# RoboFut.net
KiCad netlist of a schematic drawn in Altium Designer
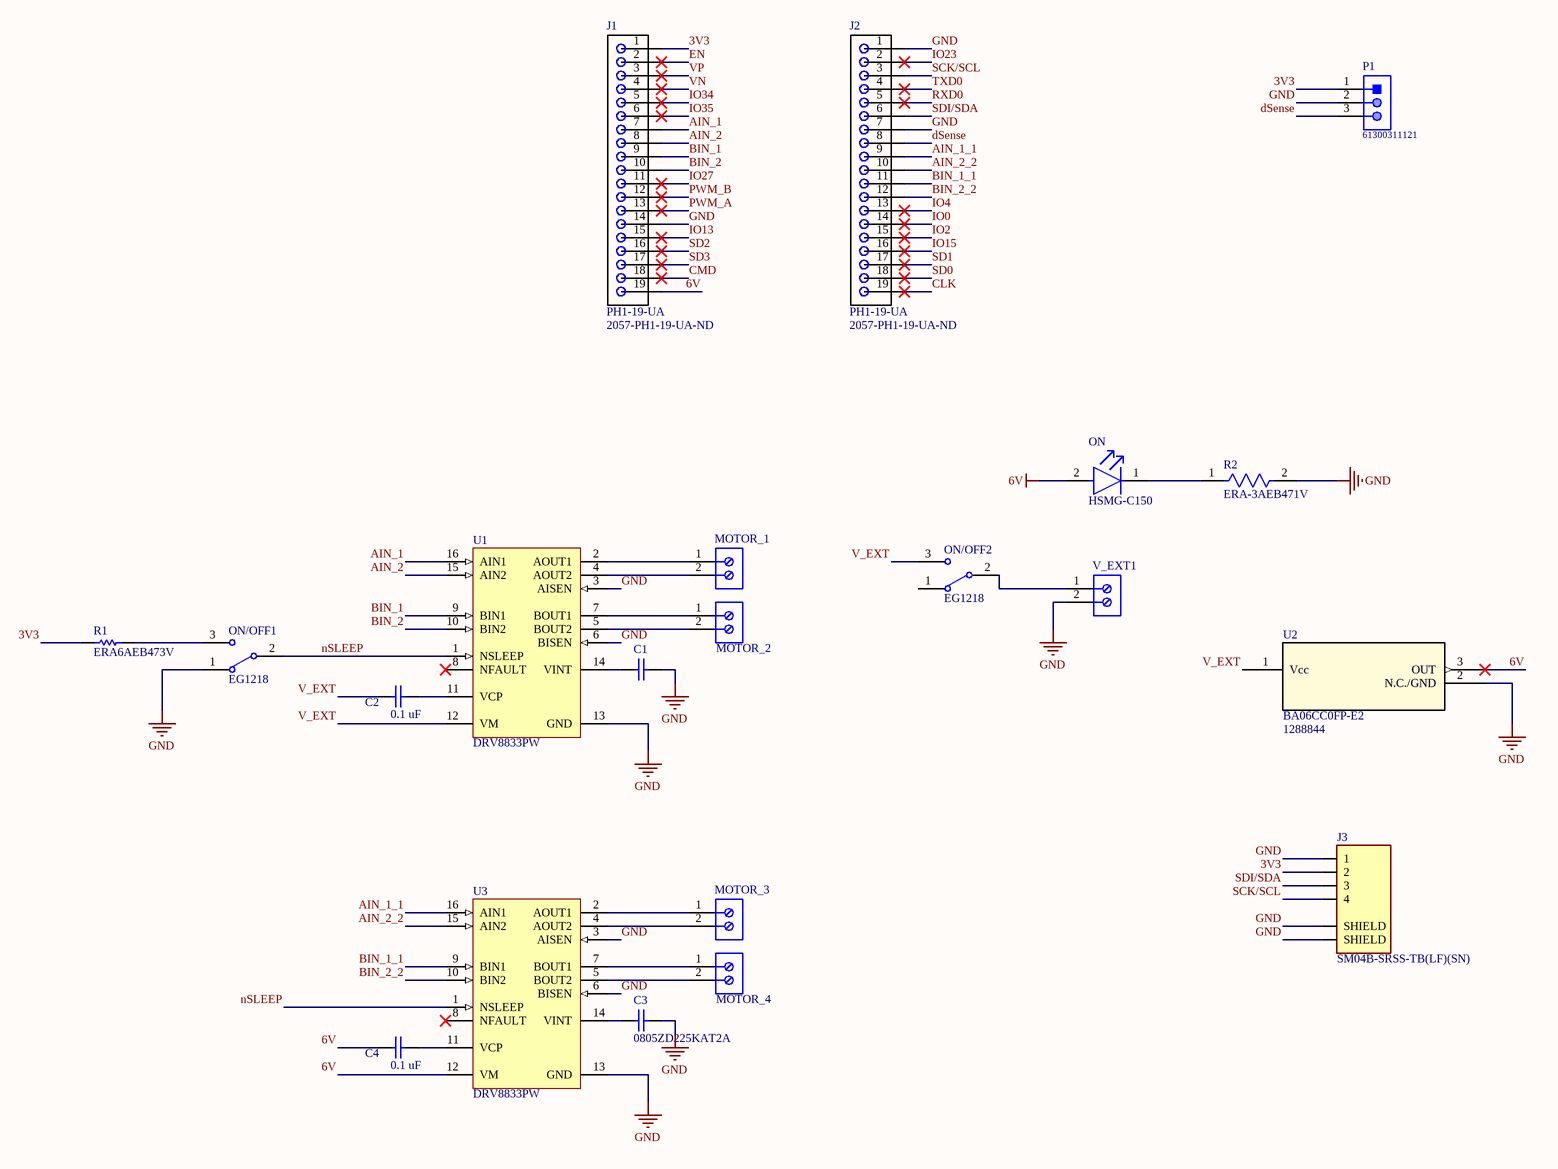
[diagram p0: RoboFut.SchDoc]

(export (version "E")
  (design (tool "Eeschema 10.0.6"))
  (components
    (comp (ref "C1")
      (value "0805ZD225KAT2A")
      (footprint "CAPC2013X140X50ML20T25")
      (description "Chip Capacitor, 2.2 uF, +/- 10%, 10 V, -55 to 85 degC, 0805 (2012 Metric), RoHS, Tape and Reel")
      (fields (field (name "MANUFACTURER") "AVX"))
      (libsource (lib "Altium Content Vault") (part "CAP-NP-2"))
    )
    (comp (ref "C2")
      (value "0.1 uF")
      (footprint "CAPC2013X94X50ML20T25")
      (description "Chip Capacitor, Ceramic, 0.1 uF, 10%, 50 V, 0805, RoHS, Tape and Reel")
      (fields (field (name "MANUFACTURER") "AVX"))
      (libsource (lib "Altium Content Vault") (part "CAP-NP-2"))
    )
    (comp (ref "C3")
      (value "0805ZD225KAT2A")
      (footprint "CAPC2013X140X50ML20T25")
      (description "Chip Capacitor, 2.2 uF, +/- 10%, 10 V, -55 to 85 degC, 0805 (2012 Metric), RoHS, Tape and Reel")
      (fields (field (name "MANUFACTURER") "AVX"))
      (libsource (lib "Altium Content Vault") (part "CAP-NP-2"))
    )
    (comp (ref "C4")
      (value "0.1 uF")
      (footprint "CAPC2013X94X50ML20T25")
      (description "Chip Capacitor, Ceramic, 0.1 uF, 10%, 50 V, 0805, RoHS, Tape and Reel")
      (fields (field (name "MANUFACTURER") "AVX"))
      (libsource (lib "Altium Content Vault") (part "CAP-NP-2"))
    )
    (comp (ref "J1")
      (value "PH1-19-UA")
      (footprint "PH1-19-UA - Socket")
      (description "Connector Header Through Hole 19 position 0.100\" (2.54mm)")
      (fields (field (name "SUPPLIER PART NUMBER 1") "2057-PH1-19-UA-ND"))
      (libsource (lib "Isidro_Library") (part "PH1-19-UA"))
    )
    (comp (ref "J2")
      (value "PH1-19-UA")
      (footprint "PH1-19-UA - Socket")
      (description "Connector Header Through Hole 19 position 0.100\" (2.54mm)")
      (fields (field (name "SUPPLIER PART NUMBER 1") "2057-PH1-19-UA-ND"))
      (libsource (lib "Isidro_Library") (part "PH1-19-UA"))
    )
    (comp (ref "J3")
      (value "SM04B-SRSS-TB(LF)(SN)")
      (footprint "JST_SM04B-SRSS-TB(LF)(SN)")
      (description "Connector Header Surface Mount, Right Angle 4 position 0.039 _1.00mm_")
      (fields (field (name "MF") "JST Sales") (field (name "MP") "SM04B-SRSS-TB_LF__SN_"))
      (libsource (lib "AQIMon") (part "SM04B-SRSS-TB(LF)(SN)"))
    )
    (comp (ref "MOTOR_1")
      (value "691214110002")
      (footprint "691214110002")
      (description "Serie 2141 - 3.50 mm Horizontal Entry Modular with Rising Cage Clamp WR-TBL, 2 pin")
      (fields (field (name "MANUFACTURER") "Wurth Elektronik") (field (name "PUBLISHER") "WurthElektronik"))
      (libsource (lib "Altium Content Vault") (part "WE-CN-1P-F-TB2"))
    )
    (comp (ref "MOTOR_2")
      (value "691214110002")
      (footprint "691214110002")
      (description "Serie 2141 - 3.50 mm Horizontal Entry Modular with Rising Cage Clamp WR-TBL, 2 pin")
      (fields (field (name "MANUFACTURER") "Wurth Elektronik") (field (name "PUBLISHER") "WurthElektronik"))
      (libsource (lib "Altium Content Vault") (part "WE-CN-1P-F-TB2"))
    )
    (comp (ref "MOTOR_3")
      (value "691214110002")
      (footprint "691214110002")
      (description "Serie 2141 - 3.50 mm Horizontal Entry Modular with Rising Cage Clamp WR-TBL, 2 pin")
      (fields (field (name "MANUFACTURER") "Wurth Elektronik") (field (name "PUBLISHER") "WurthElektronik"))
      (libsource (lib "Altium Content Vault") (part "WE-CN-1P-F-TB2"))
    )
    (comp (ref "MOTOR_4")
      (value "691214110002")
      (footprint "691214110002")
      (description "Serie 2141 - 3.50 mm Horizontal Entry Modular with Rising Cage Clamp WR-TBL, 2 pin")
      (fields (field (name "MANUFACTURER") "Wurth Elektronik") (field (name "PUBLISHER") "WurthElektronik"))
      (libsource (lib "Altium Content Vault") (part "WE-CN-1P-F-TB2"))
    )
    (comp (ref "ON")
      (value "HSMG-C150")
      (footprint "FP-HSMG-C150-MFG")
      (description "LED GREEN DIFFUSED 1206 SMD")
      (fields
        (field (name "MANUFACTURER") "Broadcom")
        (field (name "OCTOPART") "https://octopart.com/hsmg-c150-broadcom-71131304")
      )
      (libsource (lib "Altium Content Vault") (part "8706943c75ba83719d021d2fdc84c58"))
    )
    (comp (ref "ON/OFF1")
      (value "EG1218")
      (footprint "ESWI-EG1218_V")
      (description "Slide Switch, 500 V, -20 to 70 degC, 3-Pin THD, RoHS")
      (libsource (lib "Altium Content Vault") (part "SW-SPDT-3_B"))
    )
    (comp (ref "ON/OFF2")
      (value "EG1218")
      (footprint "ESWI-EG1218_V")
      (description "Slide Switch, 500 V, -20 to 70 degC, 3-Pin THD, RoHS")
      (libsource (lib "Altium Content Vault") (part "SW-SPDT-3_B"))
    )
    (comp (ref "P1")
      (value "61300311121")
      (footprint "61300311121")
      (description "THT Vertical Pin Header WR-PHD, Pitch 2.54 mm, Single Row, 3 pins")
      (fields (field (name "MANUFACTURER") "Wurth Elektronik") (field (name "PUBLISHER") "WurthElektronik"))
      (libsource (lib "Altium Content Vault") (part "WE-CN-1P-M-R3"))
    )
    (comp (ref "R1")
      (value "ERA6AEB473V")
      (footprint "RESC2013X60X40ML20T25")
      (fields (field (name "MANUFACTURER") "Panasonic"))
      (libsource (lib "Altium Content Vault") (part "RES"))
    )
    (comp (ref "R2")
      (value "ERA-3AEB471V")
      (footprint "FP-ERA3A-IPC_A")
      (description "RES SMD 470 OHM 0.1% 1/10W 0603")
      (fields (field (name "TOLERANCE") "0.1%"))
      (libsource (lib "Altium Content Vault") (part "8db39607336c341a927600551d01821"))
    )
    (comp (ref "U1")
      (value "DRV8833PW")
      (footprint "PW0016A_M")
      (fields (field (name "MANUFACTURER") "Texas Instruments"))
      (libsource (lib "Altium Content Vault") (part "TI-DRV8833PW-16"))
    )
    (comp (ref "U2")
      (value "BA06CC0FP-E2")
      (footprint "TO252-3_ROM-M")
      (description "Linear Voltage Regulator IC Positive Fixed 1 Output 1A TO-252")
      (fields
        (field (name "SUPPLIER PART NUMBER 1") "1288844")
        (field (name "COPYRIGHT") "Copyright (C) 2022 Ultra Librarian. All rights reserved.")
      )
      (libsource (lib "Isidro_Library") (part "BA06CC0FP-E2"))
    )
    (comp (ref "U3")
      (value "DRV8833PW")
      (footprint "PW0016A_M")
      (fields (field (name "MANUFACTURER") "Texas Instruments"))
      (libsource (lib "Altium Content Vault") (part "TI-DRV8833PW-16"))
    )
    (comp (ref "V_EXT1")
      (value "691214110002")
      (footprint "691214110002")
      (description "Serie 2141 - 3.50 mm Horizontal Entry Modular with Rising Cage Clamp WR-TBL, 2 pin")
      (fields (field (name "MANUFACTURER") "Wurth Elektronik") (field (name "PUBLISHER") "WurthElektronik"))
      (libsource (lib "Altium Content Vault") (part "WE-CN-1P-F-TB2"))
    )
  )
  (nets
    (net (code "1") (name "/3V3") (class "Default")
      (node (ref "J1") (pin "1") (pinfunction "1_1") (pintype "passive"))
      (node (ref "J3") (pin "2") (pinfunction "2_2") (pintype "passive"))
      (node (ref "P1") (pin "1") (pinfunction "1_1") (pintype "passive"))
      (node (ref "R1") (pin "2") (pinfunction "2_2") (pintype "passive"))
    )
    (net (code "2") (name "/AIN_1") (class "Default")
      (node (ref "J1") (pin "7") (pinfunction "7_7") (pintype "passive"))
      (node (ref "U1") (pin "16") (pinfunction "AIN1_16") (pintype "input"))
    )
    (net (code "3") (name "/AIN_1_1") (class "Default")
      (node (ref "J2") (pin "9") (pinfunction "9_9") (pintype "passive"))
      (node (ref "U3") (pin "16") (pinfunction "AIN1_16") (pintype "input"))
    )
    (net (code "4") (name "/AIN_2") (class "Default")
      (node (ref "J1") (pin "8") (pinfunction "8_8") (pintype "passive"))
      (node (ref "U1") (pin "15") (pinfunction "AIN2_15") (pintype "input"))
    )
    (net (code "5") (name "/AIN_2_2") (class "Default")
      (node (ref "J2") (pin "10") (pinfunction "10_10") (pintype "passive"))
      (node (ref "U3") (pin "15") (pinfunction "AIN2_15") (pintype "input"))
    )
    (net (code "6") (name "/BIN_1") (class "Default")
      (node (ref "J1") (pin "9") (pinfunction "9_9") (pintype "passive"))
      (node (ref "U1") (pin "9") (pinfunction "BIN1_9") (pintype "input"))
    )
    (net (code "7") (name "/BIN_1_1") (class "Default")
      (node (ref "J2") (pin "11") (pinfunction "11_11") (pintype "passive"))
      (node (ref "U3") (pin "9") (pinfunction "BIN1_9") (pintype "input"))
    )
    (net (code "8") (name "/BIN_2") (class "Default")
      (node (ref "J1") (pin "10") (pinfunction "10_10") (pintype "passive"))
      (node (ref "U1") (pin "10") (pinfunction "BIN2_10") (pintype "input"))
    )
    (net (code "9") (name "/BIN_2_2") (class "Default")
      (node (ref "J2") (pin "12") (pinfunction "12_12") (pintype "passive"))
      (node (ref "U3") (pin "10") (pinfunction "BIN2_10") (pintype "input"))
    )
    (net (code "10") (name "/CLK") (class "Default")
      (node (ref "J2") (pin "19") (pinfunction "19_19") (pintype "passive+no_connect"))
    )
    (net (code "11") (name "/CMD") (class "Default")
      (node (ref "J1") (pin "18") (pinfunction "18_18") (pintype "passive+no_connect"))
    )
    (net (code "12") (name "/EN") (class "Default")
      (node (ref "J1") (pin "2") (pinfunction "2_2") (pintype "passive+no_connect"))
    )
    (net (code "13") (name "/IO0") (class "Default")
      (node (ref "J2") (pin "14") (pinfunction "14_14") (pintype "passive+no_connect"))
    )
    (net (code "14") (name "/IO2") (class "Default")
      (node (ref "J2") (pin "15") (pinfunction "15_15") (pintype "passive+no_connect"))
    )
    (net (code "15") (name "/IO4") (class "Default")
      (node (ref "J2") (pin "13") (pinfunction "13_13") (pintype "passive+no_connect"))
    )
    (net (code "16") (name "/IO13") (class "Default")
      (node (ref "J1") (pin "15") (pinfunction "15_15") (pintype "passive+no_connect"))
    )
    (net (code "17") (name "/IO15") (class "Default")
      (node (ref "J2") (pin "16") (pinfunction "16_16") (pintype "passive+no_connect"))
    )
    (net (code "18") (name "/IO23") (class "Default")
      (node (ref "J2") (pin "2") (pinfunction "2_2") (pintype "passive+no_connect"))
    )
    (net (code "19") (name "/IO27") (class "Default")
      (node (ref "J1") (pin "11") (pinfunction "11_11") (pintype "passive+no_connect"))
    )
    (net (code "20") (name "/IO34") (class "Default")
      (node (ref "J1") (pin "5") (pinfunction "5_5") (pintype "passive+no_connect"))
    )
    (net (code "21") (name "/IO35") (class "Default")
      (node (ref "J1") (pin "6") (pinfunction "6_6") (pintype "passive+no_connect"))
    )
    (net (code "22") (name "/PWM_A") (class "Default")
      (node (ref "J1") (pin "13") (pinfunction "13_13") (pintype "passive+no_connect"))
    )
    (net (code "23") (name "/PWM_B") (class "Default")
      (node (ref "J1") (pin "12") (pinfunction "12_12") (pintype "passive+no_connect"))
    )
    (net (code "24") (name "/RXD0") (class "Default")
      (node (ref "J2") (pin "5") (pinfunction "5_5") (pintype "passive+no_connect"))
    )
    (net (code "25") (name "/SCK{slash}SCL") (class "Default")
      (node (ref "J2") (pin "3") (pinfunction "3_3") (pintype "passive"))
      (node (ref "J3") (pin "4") (pinfunction "4_4") (pintype "passive"))
    )
    (net (code "26") (name "/SD0") (class "Default")
      (node (ref "J2") (pin "18") (pinfunction "18_18") (pintype "passive+no_connect"))
    )
    (net (code "27") (name "/SD1") (class "Default")
      (node (ref "J2") (pin "17") (pinfunction "17_17") (pintype "passive+no_connect"))
    )
    (net (code "28") (name "/SD2") (class "Default")
      (node (ref "J1") (pin "16") (pinfunction "16_16") (pintype "passive+no_connect"))
    )
    (net (code "29") (name "/SD3") (class "Default")
      (node (ref "J1") (pin "17") (pinfunction "17_17") (pintype "passive+no_connect"))
    )
    (net (code "30") (name "/SDI{slash}SDA") (class "Default")
      (node (ref "J2") (pin "6") (pinfunction "6_6") (pintype "passive"))
      (node (ref "J3") (pin "3") (pinfunction "3_3") (pintype "passive"))
    )
    (net (code "31") (name "/TXD0") (class "Default")
      (node (ref "J2") (pin "4") (pinfunction "4_4") (pintype "passive+no_connect"))
    )
    (net (code "32") (name "/VN") (class "Default")
      (node (ref "J1") (pin "4") (pinfunction "4_4") (pintype "passive+no_connect"))
    )
    (net (code "33") (name "/VP") (class "Default")
      (node (ref "J1") (pin "3") (pinfunction "3_3") (pintype "passive+no_connect"))
    )
    (net (code "34") (name "/V_EXT") (class "Default")
      (node (ref "C2") (pin "2") (pinfunction "2_2") (pintype "passive"))
      (node (ref "ON/OFF2") (pin "3") (pinfunction "3_3") (pintype "passive"))
      (node (ref "U1") (pin "12") (pinfunction "VM_12") (pintype "power_in"))
      (node (ref "U2") (pin "1") (pinfunction "Vcc_1") (pintype "power_in"))
    )
    (net (code "35") (name "/dSense") (class "Default")
      (node (ref "J2") (pin "8") (pinfunction "8_8") (pintype "passive"))
      (node (ref "P1") (pin "3") (pinfunction "3_3") (pintype "passive"))
    )
    (net (code "36") (name "/nSLEEP") (class "Default")
      (node (ref "ON/OFF1") (pin "2") (pinfunction "COM_2") (pintype "passive"))
      (node (ref "U1") (pin "1") (pinfunction "NSLEEP_1") (pintype "input"))
      (node (ref "U3") (pin "1") (pinfunction "NSLEEP_1") (pintype "input"))
    )
    (net (code "37") (name "6V") (class "Default")
      (node (ref "C4") (pin "2") (pinfunction "2_2") (pintype "passive"))
      (node (ref "J1") (pin "19") (pinfunction "19_19") (pintype "passive"))
      (node (ref "ON") (pin "2") (pinfunction "A_2") (pintype "passive"))
      (node (ref "U2") (pin "3") (pinfunction "OUT_3") (pintype "output"))
      (node (ref "U3") (pin "12") (pinfunction "VM_12") (pintype "power_in"))
    )
    (net (code "38") (name "GND") (class "Default")
      (node (ref "C1") (pin "2") (pinfunction "2_2") (pintype "passive"))
      (node (ref "C3") (pin "2") (pinfunction "2_2") (pintype "passive"))
      (node (ref "J1") (pin "14") (pinfunction "14_14") (pintype "passive"))
      (node (ref "J2") (pin "1") (pinfunction "1_1") (pintype "passive"))
      (node (ref "J2") (pin "7") (pinfunction "7_7") (pintype "passive"))
      (node (ref "J3") (pin "1") (pinfunction "1_1") (pintype "passive"))
      (node (ref "J3") (pin "S1") (pinfunction "SHIELD_S1") (pintype "passive"))
      (node (ref "J3") (pin "S2") (pinfunction "SHIELD_S2") (pintype "passive"))
      (node (ref "ON/OFF1") (pin "1") (pinfunction "1_1") (pintype "passive"))
      (node (ref "P1") (pin "2") (pinfunction "2_2") (pintype "passive"))
      (node (ref "R2") (pin "2") (pinfunction "2_2") (pintype "passive"))
      (node (ref "U1") (pin "13") (pinfunction "GND_13") (pintype "power_in"))
      (node (ref "U1") (pin "3") (pinfunction "AISEN_3") (pintype "input"))
      (node (ref "U1") (pin "6") (pinfunction "BISEN_6") (pintype "input"))
      (node (ref "U2") (pin "2") (pinfunction "N.C./GND_2") (pintype "passive"))
      (node (ref "U3") (pin "13") (pinfunction "GND_13") (pintype "power_in"))
      (node (ref "U3") (pin "3") (pinfunction "AISEN_3") (pintype "input"))
      (node (ref "U3") (pin "6") (pinfunction "BISEN_6") (pintype "input"))
      (node (ref "V_EXT1") (pin "2") (pinfunction "2_2") (pintype "passive"))
    )
    (net (code "39") (name "Net-(ON-C)") (class "Default")
      (node (ref "ON") (pin "1") (pinfunction "C_1") (pintype "passive"))
      (node (ref "R2") (pin "1") (pinfunction "1_1") (pintype "passive"))
    )
    (net (code "40") (name "Net-(ON/OFF1-Pad3)") (class "Default")
      (node (ref "ON/OFF1") (pin "3") (pinfunction "3_3") (pintype "passive"))
      (node (ref "R1") (pin "1") (pinfunction "1_1") (pintype "passive"))
    )
    (net (code "41") (name "Net-(ON/OFF2-COM)") (class "Default")
      (node (ref "ON/OFF2") (pin "2") (pinfunction "COM_2") (pintype "passive"))
      (node (ref "V_EXT1") (pin "1") (pinfunction "1_1") (pintype "passive"))
    )
    (net (code "42") (name "Net-(U1-AOUT1)") (class "Default")
      (node (ref "MOTOR_1") (pin "1") (pinfunction "1_1") (pintype "passive"))
      (node (ref "U1") (pin "2") (pinfunction "AOUT1_2") (pintype "tri_state"))
    )
    (net (code "43") (name "Net-(U1-AOUT2)") (class "Default")
      (node (ref "MOTOR_1") (pin "2") (pinfunction "2_2") (pintype "passive"))
      (node (ref "U1") (pin "4") (pinfunction "AOUT2_4") (pintype "tri_state"))
    )
    (net (code "44") (name "Net-(U1-BOUT1)") (class "Default")
      (node (ref "MOTOR_2") (pin "1") (pinfunction "1_1") (pintype "passive"))
      (node (ref "U1") (pin "7") (pinfunction "BOUT1_7") (pintype "tri_state"))
    )
    (net (code "45") (name "Net-(U1-BOUT2)") (class "Default")
      (node (ref "MOTOR_2") (pin "2") (pinfunction "2_2") (pintype "passive"))
      (node (ref "U1") (pin "5") (pinfunction "BOUT2_5") (pintype "tri_state"))
    )
    (net (code "46") (name "Net-(U1-VCP)") (class "Default")
      (node (ref "C2") (pin "1") (pinfunction "1_1") (pintype "passive"))
      (node (ref "U1") (pin "11") (pinfunction "VCP_11") (pintype "passive"))
    )
    (net (code "47") (name "Net-(U1-VINT)") (class "Default")
      (node (ref "C1") (pin "1") (pinfunction "1_1") (pintype "passive"))
      (node (ref "U1") (pin "14") (pinfunction "VINT_14") (pintype "passive"))
    )
    (net (code "48") (name "Net-(U3-AOUT1)") (class "Default")
      (node (ref "MOTOR_3") (pin "1") (pinfunction "1_1") (pintype "passive"))
      (node (ref "U3") (pin "2") (pinfunction "AOUT1_2") (pintype "tri_state"))
    )
    (net (code "49") (name "Net-(U3-AOUT2)") (class "Default")
      (node (ref "MOTOR_3") (pin "2") (pinfunction "2_2") (pintype "passive"))
      (node (ref "U3") (pin "4") (pinfunction "AOUT2_4") (pintype "tri_state"))
    )
    (net (code "50") (name "Net-(U3-BOUT1)") (class "Default")
      (node (ref "MOTOR_4") (pin "1") (pinfunction "1_1") (pintype "passive"))
      (node (ref "U3") (pin "7") (pinfunction "BOUT1_7") (pintype "tri_state"))
    )
    (net (code "51") (name "Net-(U3-BOUT2)") (class "Default")
      (node (ref "MOTOR_4") (pin "2") (pinfunction "2_2") (pintype "passive"))
      (node (ref "U3") (pin "5") (pinfunction "BOUT2_5") (pintype "tri_state"))
    )
    (net (code "52") (name "Net-(U3-VCP)") (class "Default")
      (node (ref "C4") (pin "1") (pinfunction "1_1") (pintype "passive"))
      (node (ref "U3") (pin "11") (pinfunction "VCP_11") (pintype "passive"))
    )
    (net (code "53") (name "Net-(U3-VINT)") (class "Default")
      (node (ref "C3") (pin "1") (pinfunction "1_1") (pintype "passive"))
      (node (ref "U3") (pin "14") (pinfunction "VINT_14") (pintype "passive"))
    )
    (net (code "54") (name "unconnected-(ON/OFF2-Pad1)") (class "Default")
      (node (ref "ON/OFF2") (pin "1") (pinfunction "1_1") (pintype "passive"))
    )
    (net (code "55") (name "unconnected-(U1-NFAULT-Pad8)") (class "Default")
      (node (ref "U1") (pin "8") (pinfunction "NFAULT_8") (pintype "open_collector+no_connect"))
    )
    (net (code "56") (name "unconnected-(U3-NFAULT-Pad8)") (class "Default")
      (node (ref "U3") (pin "8") (pinfunction "NFAULT_8") (pintype "open_collector+no_connect"))
    )
  )
)
